# Battery_status.net
KiCad netlist of a schematic drawn in EAGLE
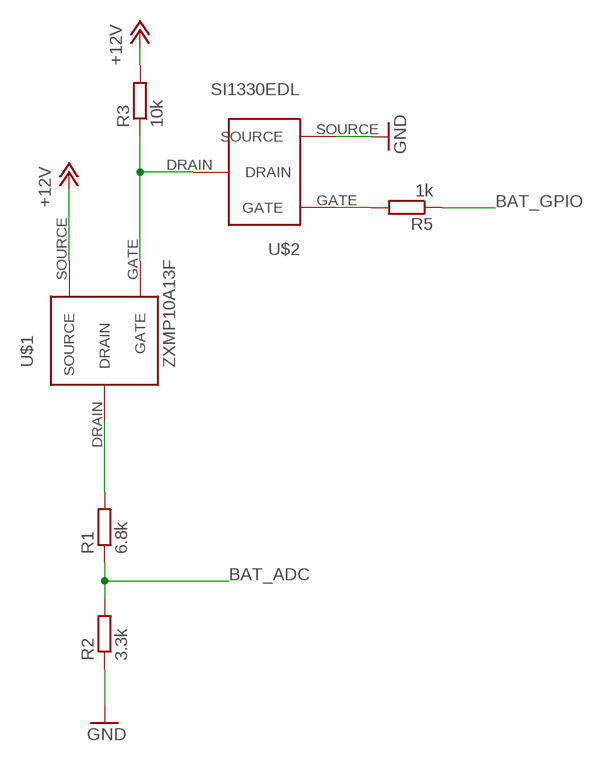
[diagram p0: schematic, sheet 1]

(export (version "E")
  (design (tool "Eeschema 10.0.6"))
  (components
    (comp (ref "R1")
      (value "6.8k")
      (footprint "eagle-import:R0805")
      (libsource (lib "eagle-import") (part "R-EU_R0805"))
    )
    (comp (ref "R2")
      (value "3.3k")
      (footprint "eagle-import:R0805")
      (libsource (lib "eagle-import") (part "R-EU_R0805"))
    )
    (comp (ref "R3")
      (value "10k")
      (footprint "eagle-import:R0805")
      (libsource (lib "eagle-import") (part "R-EU_R0805"))
    )
    (comp (ref "R5")
      (value "1k")
      (footprint "eagle-import:R0805")
      (libsource (lib "eagle-import") (part "R-EU_R0805"))
    )
    (comp (ref "U$1")
      (value "ZXMP10A13F")
      (footprint "eagle-import:P-CHANNEL")
      (libsource (lib "eagle-import") (part "ZXMP10A13F"))
    )
    (comp (ref "U$2")
      (value "SI1330EDL")
      (footprint "eagle-import:SOT-323")
      (libsource (lib "eagle-import") (part "SI1330EDL"))
    )
  )
  (nets
    (net (code "1") (name "+12V") (class "Default")
      (node (ref "R3") (pin "2") (pinfunction "2_2") (pintype "passive"))
      (node (ref "U$1") (pin "SOURCE") (pinfunction "SOURCE_SOURCE") (pintype "bidirectional"))
    )
    (net (code "2") (name "/BAT_ADC") (class "Default")
      (node (ref "R1") (pin "1") (pinfunction "1_1") (pintype "passive"))
      (node (ref "R2") (pin "2") (pinfunction "2_2") (pintype "passive"))
    )
    (net (code "3") (name "/BAT_GPIO") (class "Default")
      (node (ref "R5") (pin "1") (pinfunction "1_1") (pintype "passive"))
    )
    (net (code "4") (name "GND") (class "Default")
      (node (ref "R2") (pin "1") (pinfunction "1_1") (pintype "passive"))
      (node (ref "U$2") (pin "SOURCE") (pinfunction "SOURCE_SOURCE") (pintype "bidirectional"))
    )
    (net (code "5") (name "Net-(R1-Pad2)") (class "Default")
      (node (ref "R1") (pin "2") (pinfunction "2_2") (pintype "passive"))
      (node (ref "U$1") (pin "DRAIN") (pinfunction "DRAIN_DRAIN") (pintype "bidirectional"))
    )
    (net (code "6") (name "Net-(R3-Pad1)") (class "Default")
      (node (ref "R3") (pin "1") (pinfunction "1_1") (pintype "passive"))
      (node (ref "U$1") (pin "GATE") (pinfunction "GATE_GATE") (pintype "bidirectional"))
      (node (ref "U$2") (pin "DRAIN") (pinfunction "DRAIN_DRAIN") (pintype "bidirectional"))
    )
    (net (code "7") (name "Net-(R5-Pad2)") (class "Default")
      (node (ref "R5") (pin "2") (pinfunction "2_2") (pintype "passive"))
      (node (ref "U$2") (pin "GATE") (pinfunction "GATE_GATE") (pintype "bidirectional"))
    )
  )
)
